# mcu_v04.net
KiCad netlist of a schematic drawn in EAGLE
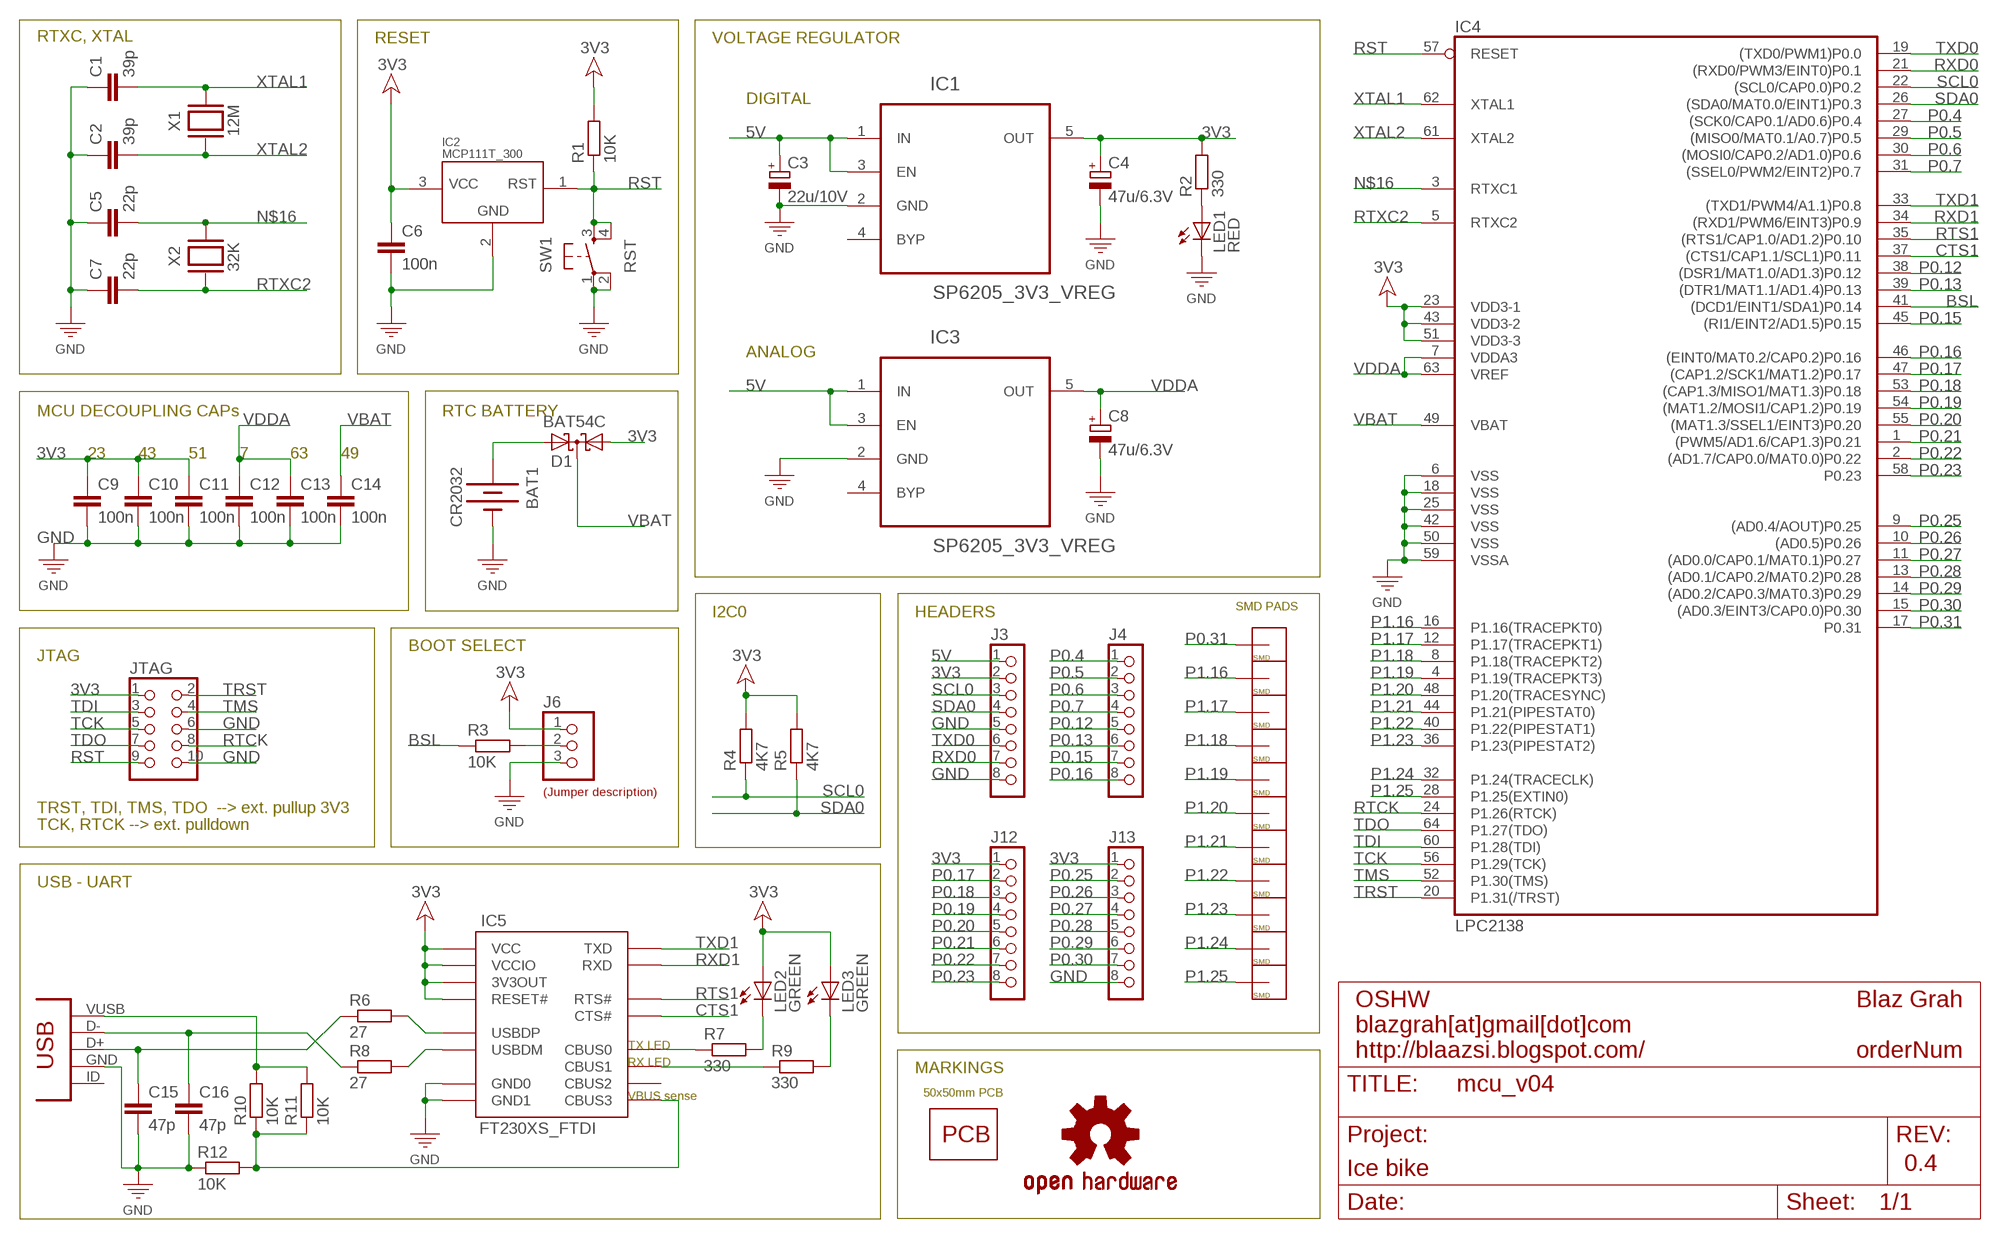
[diagram p0: schematic, sheet 1]

(export (version "E")
  (design (tool "Eeschema 10.0.6"))
  (components
    (comp (ref "BAT1")
      (value "CR2032")
      (footprint "eagle-import:BATTERY_20MM_SMD")
      (libsource (lib "eagle-import") (part "BATTERY20MM"))
    )
    (comp (ref "C1")
      (value "39p")
      (footprint "eagle-import:C0603")
      (libsource (lib "eagle-import") (part "C-EUC0603"))
    )
    (comp (ref "C2")
      (value "39p")
      (footprint "eagle-import:C0603")
      (libsource (lib "eagle-import") (part "C-EUC0603"))
    )
    (comp (ref "C3")
      (value "22u/10V")
      (footprint "eagle-import:SMC_B")
      (libsource (lib "eagle-import") (part "CAPACITOR_POL-SMC_B"))
    )
    (comp (ref "C4")
      (value "47u/6.3V")
      (footprint "eagle-import:SMC_B")
      (libsource (lib "eagle-import") (part "CAPACITOR_POL-SMC_B"))
    )
    (comp (ref "C5")
      (value "22p")
      (footprint "eagle-import:C0603")
      (libsource (lib "eagle-import") (part "C-EUC0603"))
    )
    (comp (ref "C6")
      (value "100n")
      (footprint "eagle-import:C0603")
      (libsource (lib "eagle-import") (part "C-EUC0603"))
    )
    (comp (ref "C7")
      (value "22p")
      (footprint "eagle-import:C0603")
      (libsource (lib "eagle-import") (part "C-EUC0603"))
    )
    (comp (ref "C8")
      (value "47u/6.3V")
      (footprint "eagle-import:SMC_B")
      (libsource (lib "eagle-import") (part "CAPACITOR_POL-SMC_B"))
    )
    (comp (ref "C9")
      (value "100n")
      (footprint "eagle-import:C0603")
      (libsource (lib "eagle-import") (part "C-EUC0603"))
    )
    (comp (ref "C10")
      (value "100n")
      (footprint "eagle-import:C0603")
      (libsource (lib "eagle-import") (part "C-EUC0603"))
    )
    (comp (ref "C11")
      (value "100n")
      (footprint "eagle-import:C0603")
      (libsource (lib "eagle-import") (part "C-EUC0603"))
    )
    (comp (ref "C12")
      (value "100n")
      (footprint "eagle-import:C0603")
      (libsource (lib "eagle-import") (part "C-EUC0603"))
    )
    (comp (ref "C13")
      (value "100n")
      (footprint "eagle-import:C0603")
      (libsource (lib "eagle-import") (part "C-EUC0603"))
    )
    (comp (ref "C14")
      (value "100n")
      (footprint "eagle-import:C0603")
      (libsource (lib "eagle-import") (part "C-EUC0603"))
    )
    (comp (ref "C15")
      (value "47p")
      (footprint "eagle-import:C0603")
      (libsource (lib "eagle-import") (part "C-EUC0603"))
    )
    (comp (ref "C16")
      (value "47p")
      (footprint "eagle-import:C0603")
      (libsource (lib "eagle-import") (part "C-EUC0603"))
    )
    (comp (ref "D1")
      (value "BAT54C")
      (footprint "eagle-import:SOT23")
      (libsource (lib "eagle-import") (part "BAT54C"))
    )
    (comp (ref "DOC")
      (value "FRAME_DINA4_L")
      (footprint "eagle-import:DP_LOGO")
      (fields
        (field (name "AUTHOR") "Blaz Grah")
        (field (name "LICENSE") "OSHW")
        (field (name "PROJECT") "Ice bike")
        (field (name "REV") "0.4")
        (field (name "URL1") "blazgrah[at]gmail[dot]com")
        (field (name "URL2") "http://blaazsi.blogspot.com/")
      )
      (libsource (lib "eagle-import") (part "FRAME_DINA4_L"))
    )
    (comp (ref "DSC1")
      (value "LABEL_JUMPER_1X3")
      (footprint "eagle-import:JUMP3_DESC")
      (fields (field (name "LEFT") "USER") (field (name "RIGHT") "BOOT"))
      (libsource (lib "eagle-import") (part "LABEL_JUMPER_1X3"))
    )
    (comp (ref "IC1")
      (value "SP6205_3V3_VREG")
      (footprint "eagle-import:SOT23-5")
      (libsource (lib "eagle-import") (part "SP6205_3V3_VREG"))
    )
    (comp (ref "IC2")
      (value "MCP111T_300")
      (footprint "eagle-import:SOT23")
      (libsource (lib "eagle-import") (part "MCP111T_300"))
    )
    (comp (ref "IC3")
      (value "SP6205_3V3_VREG")
      (footprint "eagle-import:SOT23-5")
      (libsource (lib "eagle-import") (part "SP6205_3V3_VREG"))
    )
    (comp (ref "IC4")
      (value "LPC2138")
      (footprint "eagle-import:LQFP64")
      (libsource (lib "eagle-import") (part "LCP2138_LQFP64"))
    )
    (comp (ref "IC5")
      (value "FT230XS_FTDI")
      (footprint "eagle-import:SSOP16")
      (libsource (lib "eagle-import") (part "FT230XS_FTDI"))
    )
    (comp (ref "J1")
      (value "CON_SMD_PAD_1X1")
      (footprint "eagle-import:CON_SMD_PAD_1_")
      (libsource (lib "eagle-import") (part "CON_SMD_PAD_1X1"))
    )
    (comp (ref "J2")
      (value "CON_SMD_PAD_1X1")
      (footprint "eagle-import:CON_SMD_PAD_1_")
      (libsource (lib "eagle-import") (part "CON_SMD_PAD_1X1"))
    )
    (comp (ref "J3")
      (value "CON_HEADER_1X08-PTH")
      (footprint "eagle-import:M1X8")
      (libsource (lib "eagle-import") (part "CON_HEADER_1X08-PTH"))
    )
    (comp (ref "J4")
      (value "CON_HEADER_1X08-PTH")
      (footprint "eagle-import:M1X8")
      (libsource (lib "eagle-import") (part "CON_HEADER_1X08-PTH"))
    )
    (comp (ref "J5")
      (value "CON_SMD_PAD_1X1")
      (footprint "eagle-import:CON_SMD_PAD_1_")
      (libsource (lib "eagle-import") (part "CON_SMD_PAD_1X1"))
    )
    (comp (ref "J6")
      (value "JUMPER_1X3ALT")
      (footprint "eagle-import:JUMPER_SOLDER")
      (libsource (lib "eagle-import") (part "JUMPER_1X3ALT"))
    )
    (comp (ref "J7")
      (value "CON_SMD_PAD_1X1")
      (footprint "eagle-import:CON_SMD_PAD_1_")
      (libsource (lib "eagle-import") (part "CON_SMD_PAD_1X1"))
    )
    (comp (ref "J8")
      (value "CON_SMD_PAD_1X1")
      (footprint "eagle-import:CON_SMD_PAD_1_")
      (libsource (lib "eagle-import") (part "CON_SMD_PAD_1X1"))
    )
    (comp (ref "J9")
      (value "CON_SMD_PAD_1X1")
      (footprint "eagle-import:CON_SMD_PAD_1_")
      (libsource (lib "eagle-import") (part "CON_SMD_PAD_1X1"))
    )
    (comp (ref "J10")
      (value "CON_SMD_PAD_1X1")
      (footprint "eagle-import:CON_SMD_PAD_1_")
      (libsource (lib "eagle-import") (part "CON_SMD_PAD_1X1"))
    )
    (comp (ref "J11")
      (value "CON_SMD_PAD_1X1")
      (footprint "eagle-import:CON_SMD_PAD_1_")
      (libsource (lib "eagle-import") (part "CON_SMD_PAD_1X1"))
    )
    (comp (ref "J12")
      (value "CON_HEADER_1X08-PTH")
      (footprint "eagle-import:M1X8")
      (libsource (lib "eagle-import") (part "CON_HEADER_1X08-PTH"))
    )
    (comp (ref "J13")
      (value "CON_HEADER_1X08-PTH")
      (footprint "eagle-import:M1X8")
      (libsource (lib "eagle-import") (part "CON_HEADER_1X08-PTH"))
    )
    (comp (ref "J14")
      (value "CON_SMD_PAD_1X1")
      (footprint "eagle-import:CON_SMD_PAD_1_")
      (libsource (lib "eagle-import") (part "CON_SMD_PAD_1X1"))
    )
    (comp (ref "J15")
      (value "CON_SMD_PAD_1X1")
      (footprint "eagle-import:CON_SMD_PAD_1_")
      (libsource (lib "eagle-import") (part "CON_SMD_PAD_1X1"))
    )
    (comp (ref "J16")
      (value "CON_SMD_PAD_1X1")
      (footprint "eagle-import:CON_SMD_PAD_1_")
      (libsource (lib "eagle-import") (part "CON_SMD_PAD_1X1"))
    )
    (comp (ref "JTAG")
      (value "CON_HEADER_2X05-PTH+SHROUDED_A")
      (footprint "eagle-import:PINSHRD_PTH_2X05")
      (libsource (lib "eagle-import") (part "CON_HEADER_2X05-PTH+SHROUDED_A"))
    )
    (comp (ref "LED1")
      (value "RED")
      (footprint "eagle-import:LED0805")
      (libsource (lib "eagle-import") (part "LED0805"))
    )
    (comp (ref "LED2")
      (value "GREEN")
      (footprint "eagle-import:LED0805")
      (libsource (lib "eagle-import") (part "LED0805"))
    )
    (comp (ref "LED3")
      (value "GREEN")
      (footprint "eagle-import:LED0805")
      (libsource (lib "eagle-import") (part "LED0805"))
    )
    (comp (ref "LOGO1")
      (value "OSHW-LOGOS")
      (footprint "eagle-import:OSHW-LOGO-S")
      (libsource (lib "eagle-import") (part "OSHW-LOGOS"))
    )
    (comp (ref "PCB1")
      (value "PCB")
      (footprint "eagle-import:PCB_50X50")
      (libsource (lib "eagle-import") (part "PCB"))
    )
    (comp (ref "R1")
      (value "10K")
      (footprint "eagle-import:R0603")
      (libsource (lib "eagle-import") (part "R-EU0603"))
    )
    (comp (ref "R2")
      (value "330")
      (footprint "eagle-import:R0603")
      (libsource (lib "eagle-import") (part "R-EU0603"))
    )
    (comp (ref "R3")
      (value "10K")
      (footprint "eagle-import:R0603")
      (libsource (lib "eagle-import") (part "R-EU0603"))
    )
    (comp (ref "R4")
      (value "4K7")
      (footprint "eagle-import:R0603")
      (libsource (lib "eagle-import") (part "R-EU0603"))
    )
    (comp (ref "R5")
      (value "4K7")
      (footprint "eagle-import:R0603")
      (libsource (lib "eagle-import") (part "R-EU0603"))
    )
    (comp (ref "R6")
      (value "27")
      (footprint "eagle-import:R0603")
      (libsource (lib "eagle-import") (part "R-EU0603"))
    )
    (comp (ref "R7")
      (value "330")
      (footprint "eagle-import:R0603")
      (libsource (lib "eagle-import") (part "R-EU0603"))
    )
    (comp (ref "R8")
      (value "27")
      (footprint "eagle-import:R0603")
      (libsource (lib "eagle-import") (part "R-EU0603"))
    )
    (comp (ref "R9")
      (value "330")
      (footprint "eagle-import:R0603")
      (libsource (lib "eagle-import") (part "R-EU0603"))
    )
    (comp (ref "R10")
      (value "10K")
      (footprint "eagle-import:R0603")
      (libsource (lib "eagle-import") (part "R-EU0603"))
    )
    (comp (ref "R11")
      (value "10K")
      (footprint "eagle-import:R0603")
      (libsource (lib "eagle-import") (part "R-EU0603"))
    )
    (comp (ref "R12")
      (value "10K")
      (footprint "eagle-import:R0603")
      (libsource (lib "eagle-import") (part "R-EU0603"))
    )
    (comp (ref "SW1")
      (value "RST")
      (footprint "eagle-import:BUTTON_SW_4P_SMD")
      (libsource (lib "eagle-import") (part "TACTIL_BUTTON"))
    )
    (comp (ref "USB1")
      (value "CON-USB-F-MINI-B")
      (footprint "eagle-import:CONN_USB_MINI-B")
      (libsource (lib "eagle-import") (part "CON-USB-F-MINI-B"))
    )
    (comp (ref "X1")
      (value "12M")
      (footprint "eagle-import:CRYSTAL_12M_4.8X10.6MM")
      (libsource (lib "eagle-import") (part "CRYSTALSMD_4.8X10.6"))
    )
    (comp (ref "X2")
      (value "32K")
      (footprint "eagle-import:CRYSTAL_32K_SMD")
      (libsource (lib "eagle-import") (part "CRYSTALSMD_32K"))
    )
  )
  (nets
    (net (code "1") (name "/5V") (class "Default")
      (node (ref "C3") (pin "+") (pinfunction "+_+") (pintype "passive"))
      (node (ref "IC1") (pin "1") (pinfunction "IN_1") (pintype "input"))
      (node (ref "IC1") (pin "3") (pinfunction "EN_3") (pintype "input"))
      (node (ref "IC3") (pin "1") (pinfunction "IN_1") (pintype "input"))
      (node (ref "IC3") (pin "3") (pinfunction "EN_3") (pintype "input"))
      (node (ref "J3") (pin "1") (pinfunction "1_1") (pintype "passive"))
    )
    (net (code "2") (name "/BSL") (class "Default")
      (node (ref "IC4") (pin "41") (pinfunction "(DCD1/EINT1/SDA1)P0.14_41") (pintype "bidirectional"))
      (node (ref "R3") (pin "1") (pinfunction "1_1") (pintype "passive"))
    )
    (net (code "3") (name "/CTS1") (class "Default")
      (node (ref "IC4") (pin "37") (pinfunction "(CTS1/CAP1.1/SCL1)P0.11_37") (pintype "bidirectional"))
      (node (ref "IC5") (pin "P$6") (pinfunction "CTS#_P$6") (pintype "bidirectional"))
    )
    (net (code "4") (name "/N$16") (class "Default")
      (node (ref "C5") (pin "2") (pinfunction "2_2") (pintype "passive"))
      (node (ref "IC4") (pin "3") (pinfunction "RTXC1_3") (pintype "input"))
      (node (ref "X2") (pin "X2") (pinfunction "2_X2") (pintype "passive"))
    )
    (net (code "5") (name "/P0.4") (class "Default")
      (node (ref "IC4") (pin "27") (pinfunction "(SCK0/CAP0.1/AD0.6)P0.4_27") (pintype "bidirectional"))
      (node (ref "J4") (pin "1") (pinfunction "1_1") (pintype "passive"))
    )
    (net (code "6") (name "/P0.5") (class "Default")
      (node (ref "IC4") (pin "29") (pinfunction "(MISO0/MAT0.1/A0.7)P0.5_29") (pintype "bidirectional"))
      (node (ref "J4") (pin "2") (pinfunction "2_2") (pintype "passive"))
    )
    (net (code "7") (name "/P0.6") (class "Default")
      (node (ref "IC4") (pin "30") (pinfunction "(MOSI0/CAP0.2/AD1.0)P0.6_30") (pintype "bidirectional"))
      (node (ref "J4") (pin "3") (pinfunction "3_3") (pintype "passive"))
    )
    (net (code "8") (name "/P0.7") (class "Default")
      (node (ref "IC4") (pin "31") (pinfunction "(SSEL0/PWM2/EINT2)P0.7_31") (pintype "bidirectional"))
      (node (ref "J4") (pin "4") (pinfunction "4_4") (pintype "passive"))
    )
    (net (code "9") (name "/P0.12") (class "Default")
      (node (ref "IC4") (pin "38") (pinfunction "(DSR1/MAT1.0/AD1.3)P0.12_38") (pintype "bidirectional"))
      (node (ref "J4") (pin "5") (pinfunction "5_5") (pintype "passive"))
    )
    (net (code "10") (name "/P0.13") (class "Default")
      (node (ref "IC4") (pin "39") (pinfunction "(DTR1/MAT1.1/AD1.4)P0.13_39") (pintype "bidirectional"))
      (node (ref "J4") (pin "6") (pinfunction "6_6") (pintype "passive"))
    )
    (net (code "11") (name "/P0.15") (class "Default")
      (node (ref "IC4") (pin "45") (pinfunction "(RI1/EINT2/AD1.5)P0.15_45") (pintype "bidirectional"))
      (node (ref "J4") (pin "7") (pinfunction "7_7") (pintype "passive"))
    )
    (net (code "12") (name "/P0.16") (class "Default")
      (node (ref "IC4") (pin "46") (pinfunction "(EINT0/MAT0.2/CAP0.2)P0.16_46") (pintype "bidirectional"))
      (node (ref "J4") (pin "8") (pinfunction "8_8") (pintype "passive"))
    )
    (net (code "13") (name "/P0.17") (class "Default")
      (node (ref "IC4") (pin "47") (pinfunction "(CAP1.2/SCK1/MAT1.2)P0.17_47") (pintype "bidirectional"))
      (node (ref "J12") (pin "2") (pinfunction "2_2") (pintype "passive"))
    )
    (net (code "14") (name "/P0.18") (class "Default")
      (node (ref "IC4") (pin "53") (pinfunction "(CAP1.3/MISO1/MAT1.3)P0.18_53") (pintype "bidirectional"))
      (node (ref "J12") (pin "3") (pinfunction "3_3") (pintype "passive"))
    )
    (net (code "15") (name "/P0.19") (class "Default")
      (node (ref "IC4") (pin "54") (pinfunction "(MAT1.2/MOSI1/CAP1.2)P0.19_54") (pintype "bidirectional"))
      (node (ref "J12") (pin "4") (pinfunction "4_4") (pintype "passive"))
    )
    (net (code "16") (name "/P0.20") (class "Default")
      (node (ref "IC4") (pin "55") (pinfunction "(MAT1.3/SSEL1/EINT3)P0.20_55") (pintype "bidirectional"))
      (node (ref "J12") (pin "5") (pinfunction "5_5") (pintype "passive"))
    )
    (net (code "17") (name "/P0.21") (class "Default")
      (node (ref "IC4") (pin "1") (pinfunction "(PWM5/AD1.6/CAP1.3)P0.21_1") (pintype "bidirectional"))
      (node (ref "J12") (pin "6") (pinfunction "6_6") (pintype "passive"))
    )
    (net (code "18") (name "/P0.22") (class "Default")
      (node (ref "IC4") (pin "2") (pinfunction "(AD1.7/CAP0.0/MAT0.0)P0.22_2") (pintype "bidirectional"))
      (node (ref "J12") (pin "7") (pinfunction "7_7") (pintype "passive"))
    )
    (net (code "19") (name "/P0.23") (class "Default")
      (node (ref "IC4") (pin "58") (pinfunction "P0.23_58") (pintype "bidirectional"))
      (node (ref "J12") (pin "8") (pinfunction "8_8") (pintype "passive"))
    )
    (net (code "20") (name "/P0.25") (class "Default")
      (node (ref "IC4") (pin "9") (pinfunction "(AD0.4/AOUT)P0.25_9") (pintype "bidirectional"))
      (node (ref "J13") (pin "2") (pinfunction "2_2") (pintype "passive"))
    )
    (net (code "21") (name "/P0.26") (class "Default")
      (node (ref "IC4") (pin "10") (pinfunction "(AD0.5)P0.26_10") (pintype "bidirectional"))
      (node (ref "J13") (pin "3") (pinfunction "3_3") (pintype "passive"))
    )
    (net (code "22") (name "/P0.27") (class "Default")
      (node (ref "IC4") (pin "11") (pinfunction "(AD0.0/CAP0.1/MAT0.1)P0.27_11") (pintype "bidirectional"))
      (node (ref "J13") (pin "4") (pinfunction "4_4") (pintype "passive"))
    )
    (net (code "23") (name "/P0.28") (class "Default")
      (node (ref "IC4") (pin "13") (pinfunction "(AD0.1/CAP0.2/MAT0.2)P0.28_13") (pintype "bidirectional"))
      (node (ref "J13") (pin "5") (pinfunction "5_5") (pintype "passive"))
    )
    (net (code "24") (name "/P0.29") (class "Default")
      (node (ref "IC4") (pin "14") (pinfunction "(AD0.2/CAP0.3/MAT0.3)P0.29_14") (pintype "bidirectional"))
      (node (ref "J13") (pin "6") (pinfunction "6_6") (pintype "passive"))
    )
    (net (code "25") (name "/P0.30") (class "Default")
      (node (ref "IC4") (pin "15") (pinfunction "(AD0.3/EINT3/CAP0.0)P0.30_15") (pintype "bidirectional"))
      (node (ref "J13") (pin "7") (pinfunction "7_7") (pintype "passive"))
    )
    (net (code "26") (name "/P0.31") (class "Default")
      (node (ref "IC4") (pin "17") (pinfunction "P0.31_17") (pintype "output"))
      (node (ref "J1") (pin "1") (pinfunction "1_1") (pintype "bidirectional"))
    )
    (net (code "27") (name "/P1.16") (class "Default")
      (node (ref "IC4") (pin "16") (pinfunction "P1.16(TRACEPKT0)_16") (pintype "bidirectional"))
      (node (ref "J2") (pin "1") (pinfunction "1_1") (pintype "bidirectional"))
    )
    (net (code "28") (name "/P1.17") (class "Default")
      (node (ref "IC4") (pin "12") (pinfunction "P1.17(TRACEPKT1)_12") (pintype "bidirectional"))
      (node (ref "J5") (pin "1") (pinfunction "1_1") (pintype "bidirectional"))
    )
    (net (code "29") (name "/P1.18") (class "Default")
      (node (ref "IC4") (pin "8") (pinfunction "P1.18(TRACEPKT2)_8") (pintype "bidirectional"))
      (node (ref "J7") (pin "1") (pinfunction "1_1") (pintype "bidirectional"))
    )
    (net (code "30") (name "/P1.19") (class "Default")
      (node (ref "IC4") (pin "4") (pinfunction "P1.19(TRACEPKT3)_4") (pintype "bidirectional"))
      (node (ref "J8") (pin "1") (pinfunction "1_1") (pintype "bidirectional"))
    )
    (net (code "31") (name "/P1.20") (class "Default")
      (node (ref "IC4") (pin "48") (pinfunction "P1.20(TRACESYNC)_48") (pintype "bidirectional"))
      (node (ref "J9") (pin "1") (pinfunction "1_1") (pintype "bidirectional"))
    )
    (net (code "32") (name "/P1.21") (class "Default")
      (node (ref "IC4") (pin "44") (pinfunction "P1.21(PIPESTAT0)_44") (pintype "bidirectional"))
      (node (ref "J10") (pin "1") (pinfunction "1_1") (pintype "bidirectional"))
    )
    (net (code "33") (name "/P1.22") (class "Default")
      (node (ref "IC4") (pin "40") (pinfunction "P1.22(PIPESTAT1)_40") (pintype "bidirectional"))
      (node (ref "J11") (pin "1") (pinfunction "1_1") (pintype "bidirectional"))
    )
    (net (code "34") (name "/P1.23") (class "Default")
      (node (ref "IC4") (pin "36") (pinfunction "P1.23(PIPESTAT2)_36") (pintype "bidirectional"))
      (node (ref "J14") (pin "1") (pinfunction "1_1") (pintype "bidirectional"))
    )
    (net (code "35") (name "/P1.24") (class "Default")
      (node (ref "IC4") (pin "32") (pinfunction "P1.24(TRACECLK)_32") (pintype "bidirectional"))
      (node (ref "J15") (pin "1") (pinfunction "1_1") (pintype "bidirectional"))
    )
    (net (code "36") (name "/P1.25") (class "Default")
      (node (ref "IC4") (pin "28") (pinfunction "P1.25(EXTIN0)_28") (pintype "bidirectional"))
      (node (ref "J16") (pin "1") (pinfunction "1_1") (pintype "bidirectional"))
    )
    (net (code "37") (name "/RST") (class "Default")
      (node (ref "IC2") (pin "1") (pinfunction "RST_1") (pintype "output"))
      (node (ref "IC4") (pin "57") (pinfunction "RESET_57") (pintype "input"))
      (node (ref "JTAG") (pin "9") (pinfunction "9_9") (pintype "passive"))
      (node (ref "R1") (pin "1") (pinfunction "1_1") (pintype "passive"))
      (node (ref "SW1") (pin "3") (pinfunction "3_3") (pintype "passive"))
      (node (ref "SW1") (pin "4") (pinfunction "4_4") (pintype "passive"))
    )
    (net (code "38") (name "/RTCK") (class "Default")
      (node (ref "IC4") (pin "24") (pinfunction "P1.26(RTCK)_24") (pintype "bidirectional"))
      (node (ref "JTAG") (pin "8") (pinfunction "8_8") (pintype "passive"))
    )
    (net (code "39") (name "/RTS1") (class "Default")
      (node (ref "IC4") (pin "35") (pinfunction "(RTS1/CAP1.0/AD1.2)P0.10_35") (pintype "bidirectional"))
      (node (ref "IC5") (pin "P$2") (pinfunction "RTS#_P$2") (pintype "bidirectional"))
    )
    (net (code "40") (name "/RTXC2") (class "Default")
      (node (ref "C7") (pin "2") (pinfunction "2_2") (pintype "passive"))
      (node (ref "IC4") (pin "5") (pinfunction "RTXC2_5") (pintype "output"))
      (node (ref "X2") (pin "X1") (pinfunction "1_X1") (pintype "passive"))
    )
    (net (code "41") (name "/RXD0") (class "Default")
      (node (ref "IC4") (pin "21") (pinfunction "(RXD0/PWM3/EINT0)P0.1_21") (pintype "bidirectional"))
      (node (ref "J3") (pin "7") (pinfunction "7_7") (pintype "passive"))
    )
    (net (code "42") (name "/RXD1") (class "Default")
      (node (ref "IC4") (pin "34") (pinfunction "(RXD1/PWM6/EINT3)P0.9_34") (pintype "bidirectional"))
      (node (ref "IC5") (pin "P$4") (pinfunction "RXD_P$4") (pintype "bidirectional"))
    )
    (net (code "43") (name "/SCL0") (class "Default")
      (node (ref "IC4") (pin "22") (pinfunction "(SCL0/CAP0.0)P0.2_22") (pintype "bidirectional"))
      (node (ref "J3") (pin "3") (pinfunction "3_3") (pintype "passive"))
      (node (ref "R4") (pin "1") (pinfunction "1_1") (pintype "passive"))
    )
    (net (code "44") (name "/SDA0") (class "Default")
      (node (ref "IC4") (pin "26") (pinfunction "(SDA0/MAT0.0/EINT1)P0.3_26") (pintype "bidirectional"))
      (node (ref "J3") (pin "4") (pinfunction "4_4") (pintype "passive"))
      (node (ref "R5") (pin "1") (pinfunction "1_1") (pintype "passive"))
    )
    (net (code "45") (name "/TCK") (class "Default")
      (node (ref "IC4") (pin "56") (pinfunction "P1.29(TCK)_56") (pintype "bidirectional"))
      (node (ref "JTAG") (pin "5") (pinfunction "5_5") (pintype "passive"))
    )
    (net (code "46") (name "/TDI") (class "Default")
      (node (ref "IC4") (pin "60") (pinfunction "P1.28(TDI)_60") (pintype "bidirectional"))
      (node (ref "JTAG") (pin "3") (pinfunction "3_3") (pintype "passive"))
    )
    (net (code "47") (name "/TDO") (class "Default")
      (node (ref "IC4") (pin "64") (pinfunction "P1.27(TDO)_64") (pintype "bidirectional"))
      (node (ref "JTAG") (pin "7") (pinfunction "7_7") (pintype "passive"))
    )
    (net (code "48") (name "/TMS") (class "Default")
      (node (ref "IC4") (pin "52") (pinfunction "P1.30(TMS)_52") (pintype "bidirectional"))
      (node (ref "JTAG") (pin "4") (pinfunction "4_4") (pintype "passive"))
    )
    (net (code "49") (name "/TRST") (class "Default")
      (node (ref "IC4") (pin "20") (pinfunction "P1.31(/TRST)_20") (pintype "bidirectional"))
      (node (ref "JTAG") (pin "2") (pinfunction "2_2") (pintype "passive"))
    )
    (net (code "50") (name "/TXD0") (class "Default")
      (node (ref "IC4") (pin "19") (pinfunction "(TXD0/PWM1)P0.0_19") (pintype "bidirectional"))
      (node (ref "J3") (pin "6") (pinfunction "6_6") (pintype "passive"))
    )
    (net (code "51") (name "/TXD1") (class "Default")
      (node (ref "IC4") (pin "33") (pinfunction "(TXD1/PWM4/A1.1)P0.8_33") (pintype "bidirectional"))
      (node (ref "IC5") (pin "P$1") (pinfunction "TXD_P$1") (pintype "bidirectional"))
    )
    (net (code "52") (name "/VBAT") (class "Default")
      (node (ref "C14") (pin "1") (pinfunction "1_1") (pintype "passive"))
      (node (ref "D1") (pin "3") (pinfunction "CC_3") (pintype "passive"))
      (node (ref "IC4") (pin "49") (pinfunction "VBAT_49") (pintype "power_in"))
    )
    (net (code "53") (name "/VDDA") (class "Default")
      (node (ref "C12") (pin "1") (pinfunction "1_1") (pintype "passive"))
      (node (ref "C13") (pin "1") (pinfunction "1_1") (pintype "passive"))
      (node (ref "C8") (pin "+") (pinfunction "+_+") (pintype "passive"))
      (node (ref "IC3") (pin "5") (pinfunction "OUT_5") (pintype "power_in"))
      (node (ref "IC4") (pin "63") (pinfunction "VREF_63") (pintype "input"))
      (node (ref "IC4") (pin "7") (pinfunction "VDDA3_7") (pintype "power_in"))
    )
    (net (code "54") (name "/XTAL1") (class "Default")
      (node (ref "C1") (pin "2") (pinfunction "2_2") (pintype "passive"))
      (node (ref "IC4") (pin "62") (pinfunction "XTAL1_62") (pintype "input"))
      (node (ref "X1") (pin "P$2") (pinfunction "2_P$2") (pintype "passive"))
    )
    (net (code "55") (name "/XTAL2") (class "Default")
      (node (ref "C2") (pin "2") (pinfunction "2_2") (pintype "passive"))
      (node (ref "IC4") (pin "61") (pinfunction "XTAL2_61") (pintype "output"))
      (node (ref "X1") (pin "P$1") (pinfunction "1_P$1") (pintype "passive"))
    )
    (net (code "56") (name "3V3") (class "Default")
      (node (ref "C10") (pin "1") (pinfunction "1_1") (pintype "passive"))
      (node (ref "C11") (pin "1") (pinfunction "1_1") (pintype "passive"))
      (node (ref "C4") (pin "+") (pinfunction "+_+") (pintype "passive"))
      (node (ref "C6") (pin "1") (pinfunction "1_1") (pintype "passive"))
      (node (ref "C9") (pin "1") (pinfunction "1_1") (pintype "passive"))
      (node (ref "D1") (pin "1") (pinfunction "A1_1") (pintype "passive"))
      (node (ref "IC1") (pin "5") (pinfunction "OUT_5") (pintype "power_in"))
      (node (ref "IC2") (pin "3") (pinfunction "VCC_3") (pintype "input"))
      (node (ref "IC4") (pin "23") (pinfunction "VDD3-1_23") (pintype "power_in"))
      (node (ref "IC4") (pin "43") (pinfunction "VDD3-2_43") (pintype "power_in"))
      (node (ref "IC4") (pin "51") (pinfunction "VDD3-3_51") (pintype "power_in"))
      (node (ref "IC5") (pin "P$10") (pinfunction "3V3OUT_P$10") (pintype "power_in"))
      (node (ref "IC5") (pin "P$11") (pinfunction "RESET#_P$11") (pintype "bidirectional"))
      (node (ref "IC5") (pin "P$12") (pinfunction "VCC_P$12") (pintype "power_in"))
      (node (ref "IC5") (pin "P$3") (pinfunction "VCCIO_P$3") (pintype "power_in"))
      (node (ref "J12") (pin "1") (pinfunction "1_1") (pintype "passive"))
      (node (ref "J13") (pin "1") (pinfunction "1_1") (pintype "passive"))
      (node (ref "J3") (pin "2") (pinfunction "2_2") (pintype "passive"))
      (node (ref "J6") (pin "1") (pinfunction "1_1") (pintype "passive"))
      (node (ref "JTAG") (pin "1") (pinfunction "1_1") (pintype "passive"))
      (node (ref "LED2") (pin "A") (pinfunction "A_A") (pintype "passive"))
      (node (ref "LED3") (pin "A") (pinfunction "A_A") (pintype "passive"))
      (node (ref "R1") (pin "2") (pinfunction "2_2") (pintype "passive"))
      (node (ref "R2") (pin "2") (pinfunction "2_2") (pintype "passive"))
      (node (ref "R4") (pin "2") (pinfunction "2_2") (pintype "passive"))
      (node (ref "R5") (pin "2") (pinfunction "2_2") (pintype "passive"))
    )
    (net (code "57") (name "GND") (class "Default")
      (node (ref "BAT1") (pin "NEG") (pinfunction "NEG_NEG") (pintype "power_in"))
      (node (ref "C1") (pin "1") (pinfunction "1_1") (pintype "passive"))
      (node (ref "C10") (pin "2") (pinfunction "2_2") (pintype "passive"))
      (node (ref "C11") (pin "2") (pinfunction "2_2") (pintype "passive"))
      (node (ref "C12") (pin "2") (pinfunction "2_2") (pintype "passive"))
      (node (ref "C13") (pin "2") (pinfunction "2_2") (pintype "passive"))
      (node (ref "C14") (pin "2") (pinfunction "2_2") (pintype "passive"))
      (node (ref "C15") (pin "2") (pinfunction "2_2") (pintype "passive"))
      (node (ref "C16") (pin "2") (pinfunction "2_2") (pintype "passive"))
      (node (ref "C2") (pin "1") (pinfunction "1_1") (pintype "passive"))
      (node (ref "C3") (pin "-") (pinfunction "-_-") (pintype "passive"))
      (node (ref "C4") (pin "-") (pinfunction "-_-") (pintype "passive"))
      (node (ref "C5") (pin "1") (pinfunction "1_1") (pintype "passive"))
      (node (ref "C6") (pin "2") (pinfunction "2_2") (pintype "passive"))
      (node (ref "C7") (pin "1") (pinfunction "1_1") (pintype "passive"))
      (node (ref "C8") (pin "-") (pinfunction "-_-") (pintype "passive"))
      (node (ref "C9") (pin "2") (pinfunction "2_2") (pintype "passive"))
      (node (ref "IC1") (pin "2") (pinfunction "GND_2") (pintype "power_in"))
      (node (ref "IC2") (pin "2") (pinfunction "GND_2") (pintype "power_in"))
      (node (ref "IC3") (pin "2") (pinfunction "GND_2") (pintype "power_in"))
      (node (ref "IC4") (pin "18") (pinfunction "VSS_18") (pintype "power_in"))
      (node (ref "IC4") (pin "25") (pinfunction "VSS_25") (pintype "power_in"))
      (node (ref "IC4") (pin "42") (pinfunction "VSS_42") (pintype "power_in"))
      (node (ref "IC4") (pin "50") (pinfunction "VSS_50") (pintype "power_in"))
      (node (ref "IC4") (pin "59") (pinfunction "VSSA_59") (pintype "power_in"))
      (node (ref "IC4") (pin "6") (pinfunction "VSS_6") (pintype "power_in"))
      (node (ref "IC5") (pin "P$13") (pinfunction "GND1_P$13") (pintype "power_in"))
      (node (ref "IC5") (pin "P$5") (pinfunction "GND0_P$5") (pintype "power_in"))
      (node (ref "J13") (pin "8") (pinfunction "8_8") (pintype "passive"))
      (node (ref "J3") (pin "5") (pinfunction "5_5") (pintype "passive"))
      (node (ref "J3") (pin "8") (pinfunction "8_8") (pintype "passive"))
      (node (ref "J6") (pin "3") (pinfunction "3_3") (pintype "passive"))
      (node (ref "JTAG") (pin "10") (pinfunction "10_10") (pintype "passive"))
      (node (ref "JTAG") (pin "6") (pinfunction "6_6") (pintype "passive"))
      (node (ref "LED1") (pin "C") (pinfunction "C_C") (pintype "passive"))
      (node (ref "R12") (pin "1") (pinfunction "1_1") (pintype "passive"))
      (node (ref "SW1") (pin "1") (pinfunction "1_1") (pintype "passive"))
      (node (ref "SW1") (pin "2") (pinfunction "2_2") (pintype "passive"))
      (node (ref "USB1") (pin "GND") (pinfunction "GND_GND") (pintype "bidirectional"))
    )
    (net (code "58") (name "Net-(C15-Pad1)") (class "Default")
      (node (ref "C15") (pin "1") (pinfunction "1_1") (pintype "passive"))
      (node (ref "R6") (pin "1") (pinfunction "1_1") (pintype "passive"))
      (node (ref "USB1") (pin "D+") (pinfunction "D+_D+") (pintype "bidirectional"))
    )
    (net (code "59") (name "Net-(C16-Pad1)") (class "Default")
      (node (ref "C16") (pin "1") (pinfunction "1_1") (pintype "passive"))
      (node (ref "R8") (pin "1") (pinfunction "1_1") (pintype "passive"))
      (node (ref "USB1") (pin "D-") (pinfunction "D-_D-") (pintype "bidirectional"))
    )
    (net (code "60") (name "Net-(D1-A2)") (class "Default")
      (node (ref "BAT1") (pin "POS1") (pinfunction "POZ_POS1") (pintype "power_in"))
      (node (ref "BAT1") (pin "POS2") (pinfunction "POZ_POS2") (pintype "power_in"))
      (node (ref "D1") (pin "2") (pinfunction "A2_2") (pintype "passive"))
    )
    (net (code "61") (name "Net-(IC5-CBUS0)") (class "Default")
      (node (ref "IC5") (pin "P$15") (pinfunction "CBUS0_P$15") (pintype "bidirectional"))
      (node (ref "R7") (pin "1") (pinfunction "1_1") (pintype "passive"))
    )
    (net (code "62") (name "Net-(IC5-CBUS1)") (class "Default")
      (node (ref "IC5") (pin "P$14") (pinfunction "CBUS1_P$14") (pintype "bidirectional"))
      (node (ref "R9") (pin "1") (pinfunction "1_1") (pintype "passive"))
    )
    (net (code "63") (name "Net-(IC5-CBUS3)") (class "Default")
      (node (ref "IC5") (pin "P$16") (pinfunction "CBUS3_P$16") (pintype "bidirectional"))
      (node (ref "R10") (pin "1") (pinfunction "1_1") (pintype "passive"))
      (node (ref "R11") (pin "1") (pinfunction "1_1") (pintype "passive"))
      (node (ref "R12") (pin "2") (pinfunction "2_2") (pintype "passive"))
    )
    (net (code "64") (name "Net-(IC5-USBDM)") (class "Default")
      (node (ref "IC5") (pin "P$9") (pinfunction "USBDM_P$9") (pintype "bidirectional"))
      (node (ref "R8") (pin "2") (pinfunction "2_2") (pintype "passive"))
    )
    (net (code "65") (name "Net-(IC5-USBDP)") (class "Default")
      (node (ref "IC5") (pin "P$8") (pinfunction "USBDP_P$8") (pintype "bidirectional"))
      (node (ref "R6") (pin "2") (pinfunction "2_2") (pintype "passive"))
    )
    (net (code "66") (name "Net-(J6-Pad2)") (class "Default")
      (node (ref "J6") (pin "2") (pinfunction "2_2") (pintype "passive"))
      (node (ref "R3") (pin "2") (pinfunction "2_2") (pintype "passive"))
    )
    (net (code "67") (name "Net-(LED1-PadA)") (class "Default")
      (node (ref "LED1") (pin "A") (pinfunction "A_A") (pintype "passive"))
      (node (ref "R2") (pin "1") (pinfunction "1_1") (pintype "passive"))
    )
    (net (code "68") (name "Net-(LED2-PadC)") (class "Default")
      (node (ref "LED2") (pin "C") (pinfunction "C_C") (pintype "passive"))
      (node (ref "R7") (pin "2") (pinfunction "2_2") (pintype "passive"))
    )
    (net (code "69") (name "Net-(LED3-PadC)") (class "Default")
      (node (ref "LED3") (pin "C") (pinfunction "C_C") (pintype "passive"))
      (node (ref "R9") (pin "2") (pinfunction "2_2") (pintype "passive"))
    )
    (net (code "70") (name "Net-(R10-Pad2)") (class "Default")
      (node (ref "R10") (pin "2") (pinfunction "2_2") (pintype "passive"))
      (node (ref "R11") (pin "2") (pinfunction "2_2") (pintype "passive"))
      (node (ref "USB1") (pin "VUSB") (pinfunction "VUSB_VUSB") (pintype "bidirectional"))
    )
    (net (code "71") (name "unconnected-(IC1-BYP-Pad4)") (class "Default")
      (node (ref "IC1") (pin "4") (pinfunction "BYP_4") (pintype "no_connect"))
    )
    (net (code "72") (name "unconnected-(IC3-BYP-Pad4)") (class "Default")
      (node (ref "IC3") (pin "4") (pinfunction "BYP_4") (pintype "no_connect"))
    )
    (net (code "73") (name "unconnected-(IC5-CBUS2-PadP$7)") (class "Default")
      (node (ref "IC5") (pin "P$7") (pinfunction "CBUS2_P$7") (pintype "bidirectional"))
    )
    (net (code "74") (name "unconnected-(USB1B-USBID-PadID)") (class "Default")
      (node (ref "USB1") (pin "ID") (pinfunction "USBID_ID") (pintype "bidirectional"))
    )
  )
)
